# CT.net
KiCad netlist of a schematic drawn in EasyEDA
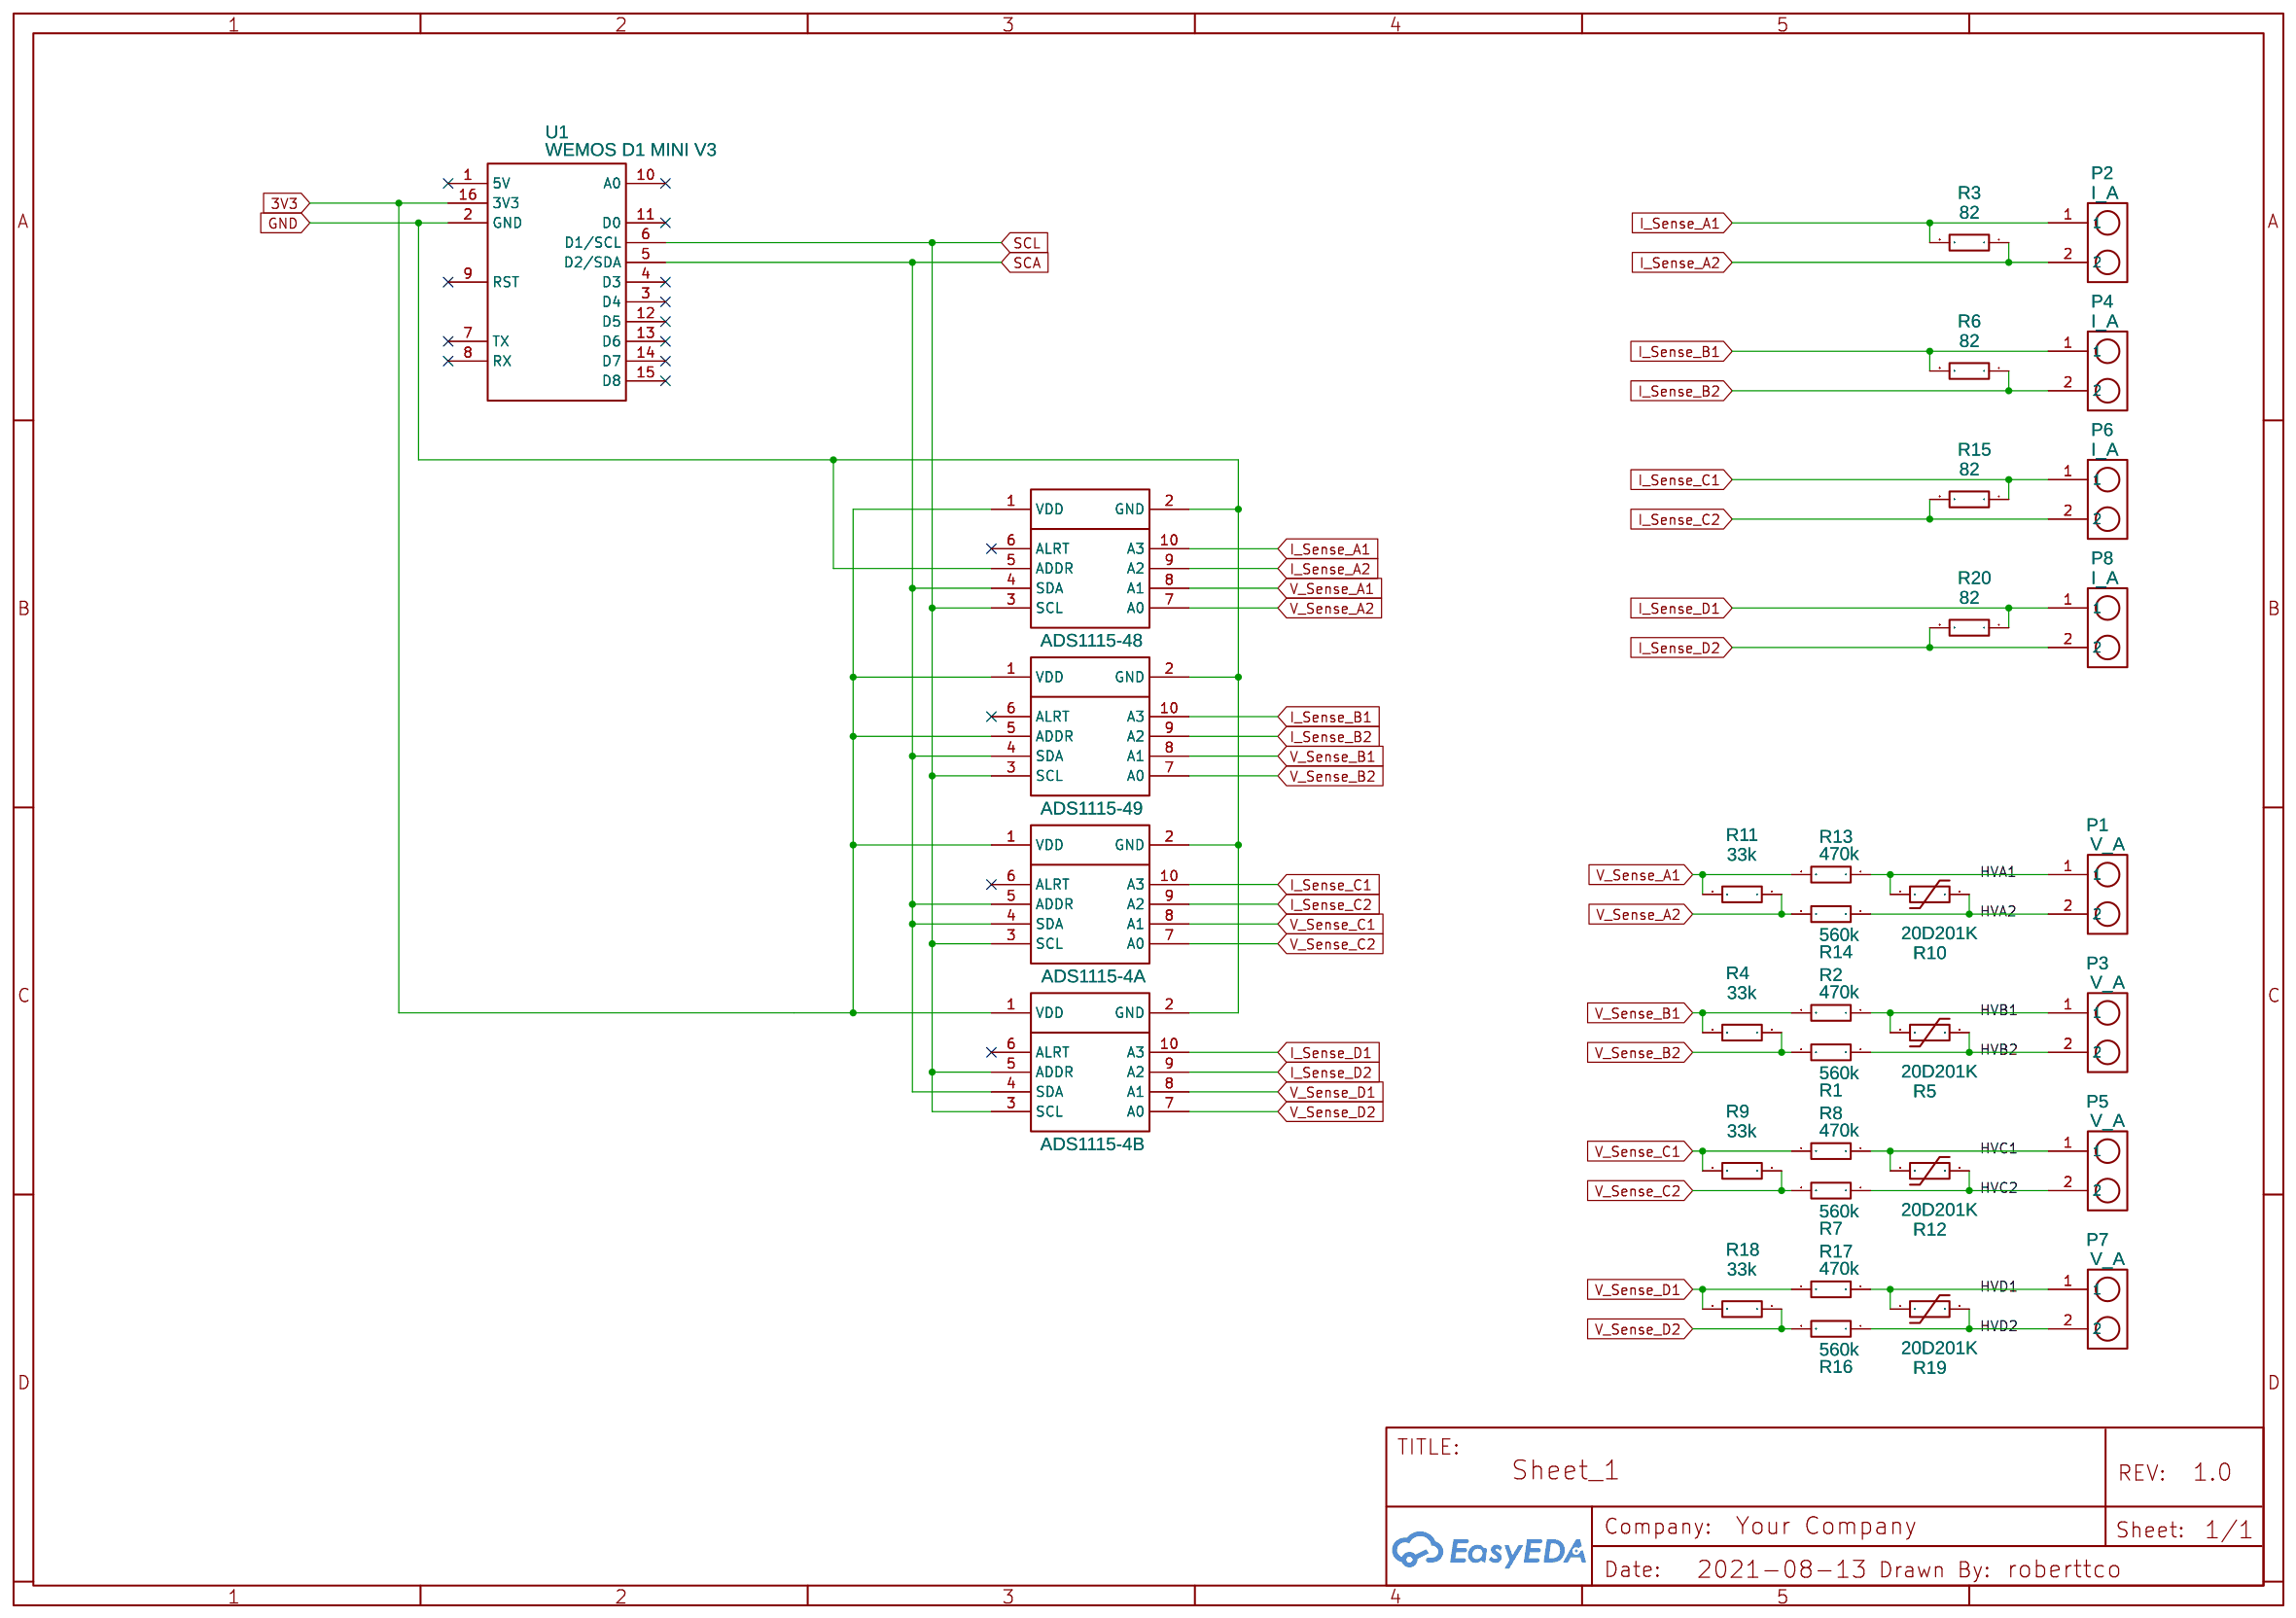
[diagram p0: schematic sheet]

(export (version "E")
  (design (tool "Eeschema 10.0.6"))
  (components
    (comp (ref "A1") (value "ADS1115-49") (libsource (lib "") (part "ADS1115")))
    (comp (ref "A2") (value "ADS1115-4A") (libsource (lib "") (part "ADS1115")))
    (comp (ref "A3") (value "ADS1115-4B") (libsource (lib "") (part "ADS1115")))
    (comp (ref "A4") (value "ADS1115-48") (libsource (lib "") (part "ADS1115")))
    (comp (ref "P1")
      (value "V_A")
      (fields (field (name "BOM_Manufacturer Part") "DW"))
      (libsource (lib "") (part "Screw Connector x2"))
    )
    (comp (ref "P2")
      (value "I_A")
      (fields (field (name "BOM_Manufacturer Part") "DW"))
      (libsource (lib "") (part "Screw Connector x2"))
    )
    (comp (ref "P3")
      (value "V_A")
      (fields (field (name "BOM_Manufacturer Part") "DW"))
      (libsource (lib "") (part "Screw Connector x2"))
    )
    (comp (ref "P4")
      (value "I_A")
      (fields (field (name "BOM_Manufacturer Part") "DW"))
      (libsource (lib "") (part "Screw Connector x2"))
    )
    (comp (ref "P5")
      (value "V_A")
      (fields (field (name "BOM_Manufacturer Part") "DW"))
      (libsource (lib "") (part "Screw Connector x2"))
    )
    (comp (ref "P6")
      (value "I_A")
      (fields (field (name "BOM_Manufacturer Part") "DW"))
      (libsource (lib "") (part "Screw Connector x2"))
    )
    (comp (ref "P7")
      (value "V_A")
      (fields (field (name "BOM_Manufacturer Part") "DW"))
      (libsource (lib "") (part "Screw Connector x2"))
    )
    (comp (ref "P8")
      (value "I_A")
      (fields (field (name "BOM_Manufacturer Part") "DW"))
      (libsource (lib "") (part "Screw Connector x2"))
    )
    (comp (ref "R1")
      (value "560k")
      (fields (field (name "BOM_Supplier Part") "C119347"))
      (libsource (lib "") (part "RESISTOR"))
    )
    (comp (ref "R2")
      (value "470k")
      (fields (field (name "BOM_Supplier Part") "C119347"))
      (libsource (lib "") (part "RESISTOR"))
    )
    (comp (ref "R3")
      (value "82")
      (fields (field (name "BOM_Supplier Part") "C119347"))
      (libsource (lib "") (part "RESISTOR"))
    )
    (comp (ref "R4")
      (value "33k")
      (fields (field (name "BOM_Supplier Part") "C119347"))
      (libsource (lib "") (part "RESISTOR"))
    )
    (comp (ref "R5")
      (value "20D201K")
      (fields (field (name "BOM_Supplier Part") "C317857"))
      (libsource (lib "") (part "20D201K"))
    )
    (comp (ref "R6")
      (value "82")
      (fields (field (name "BOM_Supplier Part") "C119347"))
      (libsource (lib "") (part "RESISTOR"))
    )
    (comp (ref "R7")
      (value "560k")
      (fields (field (name "BOM_Supplier Part") "C119347"))
      (libsource (lib "") (part "RESISTOR"))
    )
    (comp (ref "R8")
      (value "470k")
      (fields (field (name "BOM_Supplier Part") "C119347"))
      (libsource (lib "") (part "RESISTOR"))
    )
    (comp (ref "R9")
      (value "33k")
      (fields (field (name "BOM_Supplier Part") "C119347"))
      (libsource (lib "") (part "RESISTOR"))
    )
    (comp (ref "R10")
      (value "20D201K")
      (fields (field (name "BOM_Supplier Part") "C317857"))
      (libsource (lib "") (part "20D201K"))
    )
    (comp (ref "R11")
      (value "33k")
      (fields (field (name "BOM_Supplier Part") "C119347"))
      (libsource (lib "") (part "RESISTOR"))
    )
    (comp (ref "R12")
      (value "20D201K")
      (fields (field (name "BOM_Supplier Part") "C317857"))
      (libsource (lib "") (part "20D201K"))
    )
    (comp (ref "R13")
      (value "470k")
      (fields (field (name "BOM_Supplier Part") "C119347"))
      (libsource (lib "") (part "RESISTOR"))
    )
    (comp (ref "R14")
      (value "560k")
      (fields (field (name "BOM_Supplier Part") "C119347"))
      (libsource (lib "") (part "RESISTOR"))
    )
    (comp (ref "R15")
      (value "82")
      (fields (field (name "BOM_Supplier Part") "C119347"))
      (libsource (lib "") (part "RESISTOR"))
    )
    (comp (ref "R16")
      (value "560k")
      (fields (field (name "BOM_Supplier Part") "C119347"))
      (libsource (lib "") (part "RESISTOR"))
    )
    (comp (ref "R17")
      (value "470k")
      (fields (field (name "BOM_Supplier Part") "C119347"))
      (libsource (lib "") (part "RESISTOR"))
    )
    (comp (ref "R18")
      (value "33k")
      (fields (field (name "BOM_Supplier Part") "C119347"))
      (libsource (lib "") (part "RESISTOR"))
    )
    (comp (ref "R19")
      (value "20D201K")
      (fields (field (name "BOM_Supplier Part") "C317857"))
      (libsource (lib "") (part "20D201K"))
    )
    (comp (ref "R20")
      (value "82")
      (fields (field (name "BOM_Supplier Part") "C119347"))
      (libsource (lib "") (part "RESISTOR"))
    )
    (comp (ref "U1")
      (value "WEMOS D1 MINI V3")
      (fields (field (name "BOM_Manufacturer Part") "Wemos D1 mini"))
      (libsource (lib "") (part "WEMOS D1 MINI V3"))
    )
  )
  (nets
    (net (code "1") (name "/HVA1") (class "Default")
      (node (ref "P1") (pin "1") (pinfunction "1_1") (pintype "unspecified"))
      (node (ref "R10") (pin "1") (pinfunction "1_1") (pintype "unspecified"))
      (node (ref "R13") (pin "1") (pinfunction "1_1") (pintype "unspecified"))
    )
    (net (code "2") (name "/HVA2") (class "Default")
      (node (ref "P1") (pin "2") (pinfunction "2_2") (pintype "unspecified"))
      (node (ref "R10") (pin "2") (pinfunction "2_2") (pintype "unspecified"))
      (node (ref "R14") (pin "1") (pinfunction "1_1") (pintype "unspecified"))
    )
    (net (code "3") (name "/HVB1") (class "Default")
      (node (ref "P3") (pin "1") (pinfunction "1_1") (pintype "unspecified"))
      (node (ref "R2") (pin "1") (pinfunction "1_1") (pintype "unspecified"))
      (node (ref "R5") (pin "1") (pinfunction "1_1") (pintype "unspecified"))
    )
    (net (code "4") (name "/HVB2") (class "Default")
      (node (ref "P3") (pin "2") (pinfunction "2_2") (pintype "unspecified"))
      (node (ref "R1") (pin "1") (pinfunction "1_1") (pintype "unspecified"))
      (node (ref "R5") (pin "2") (pinfunction "2_2") (pintype "unspecified"))
    )
    (net (code "5") (name "/HVC1") (class "Default")
      (node (ref "P5") (pin "1") (pinfunction "1_1") (pintype "unspecified"))
      (node (ref "R12") (pin "1") (pinfunction "1_1") (pintype "unspecified"))
      (node (ref "R8") (pin "1") (pinfunction "1_1") (pintype "unspecified"))
    )
    (net (code "6") (name "/HVC2") (class "Default")
      (node (ref "P5") (pin "2") (pinfunction "2_2") (pintype "unspecified"))
      (node (ref "R12") (pin "2") (pinfunction "2_2") (pintype "unspecified"))
      (node (ref "R7") (pin "1") (pinfunction "1_1") (pintype "unspecified"))
    )
    (net (code "7") (name "/HVD1") (class "Default")
      (node (ref "P7") (pin "1") (pinfunction "1_1") (pintype "unspecified"))
      (node (ref "R17") (pin "1") (pinfunction "1_1") (pintype "unspecified"))
      (node (ref "R19") (pin "1") (pinfunction "1_1") (pintype "unspecified"))
    )
    (net (code "8") (name "/HVD2") (class "Default")
      (node (ref "P7") (pin "2") (pinfunction "2_2") (pintype "unspecified"))
      (node (ref "R16") (pin "1") (pinfunction "1_1") (pintype "unspecified"))
      (node (ref "R19") (pin "2") (pinfunction "2_2") (pintype "unspecified"))
    )
    (net (code "9") (name "3V3") (class "Default")
      (node (ref "A1") (pin "1") (pinfunction "VDD_1") (pintype "passive"))
      (node (ref "A1") (pin "5") (pinfunction "ADDR_5") (pintype "output"))
      (node (ref "A2") (pin "1") (pinfunction "VDD_1") (pintype "passive"))
      (node (ref "A3") (pin "1") (pinfunction "VDD_1") (pintype "passive"))
      (node (ref "A4") (pin "1") (pinfunction "VDD_1") (pintype "passive"))
      (node (ref "U1") (pin "16") (pinfunction "3V3_16") (pintype "unspecified"))
    )
    (net (code "10") (name "GND") (class "Default")
      (node (ref "A1") (pin "2") (pinfunction "GND_2") (pintype "passive"))
      (node (ref "A2") (pin "2") (pinfunction "GND_2") (pintype "passive"))
      (node (ref "A3") (pin "2") (pinfunction "GND_2") (pintype "passive"))
      (node (ref "A4") (pin "2") (pinfunction "GND_2") (pintype "passive"))
      (node (ref "A4") (pin "5") (pinfunction "ADDR_5") (pintype "output"))
      (node (ref "U1") (pin "2") (pinfunction "GND_2") (pintype "unspecified"))
    )
    (net (code "11") (name "I_Sense_A1") (class "Default")
      (node (ref "A4") (pin "10") (pinfunction "A3_10") (pintype "input"))
      (node (ref "P2") (pin "1") (pinfunction "1_1") (pintype "unspecified"))
      (node (ref "R3") (pin "2") (pinfunction "2_2") (pintype "unspecified"))
    )
    (net (code "12") (name "I_Sense_A2") (class "Default")
      (node (ref "A4") (pin "9") (pinfunction "A2_9") (pintype "input"))
      (node (ref "P2") (pin "2") (pinfunction "2_2") (pintype "unspecified"))
      (node (ref "R3") (pin "1") (pinfunction "1_1") (pintype "unspecified"))
    )
    (net (code "13") (name "I_Sense_B1") (class "Default")
      (node (ref "A1") (pin "10") (pinfunction "A3_10") (pintype "input"))
      (node (ref "P4") (pin "1") (pinfunction "1_1") (pintype "unspecified"))
      (node (ref "R6") (pin "2") (pinfunction "2_2") (pintype "unspecified"))
    )
    (net (code "14") (name "I_Sense_B2") (class "Default")
      (node (ref "A1") (pin "9") (pinfunction "A2_9") (pintype "input"))
      (node (ref "P4") (pin "2") (pinfunction "2_2") (pintype "unspecified"))
      (node (ref "R6") (pin "1") (pinfunction "1_1") (pintype "unspecified"))
    )
    (net (code "15") (name "I_Sense_C1") (class "Default")
      (node (ref "A2") (pin "10") (pinfunction "A3_10") (pintype "input"))
      (node (ref "P6") (pin "1") (pinfunction "1_1") (pintype "unspecified"))
      (node (ref "R15") (pin "1") (pinfunction "1_1") (pintype "unspecified"))
    )
    (net (code "16") (name "I_Sense_C2") (class "Default")
      (node (ref "A2") (pin "9") (pinfunction "A2_9") (pintype "input"))
      (node (ref "P6") (pin "2") (pinfunction "2_2") (pintype "unspecified"))
      (node (ref "R15") (pin "2") (pinfunction "2_2") (pintype "unspecified"))
    )
    (net (code "17") (name "I_Sense_D1") (class "Default")
      (node (ref "A3") (pin "10") (pinfunction "A3_10") (pintype "input"))
      (node (ref "P8") (pin "1") (pinfunction "1_1") (pintype "unspecified"))
      (node (ref "R20") (pin "1") (pinfunction "1_1") (pintype "unspecified"))
    )
    (net (code "18") (name "I_Sense_D2") (class "Default")
      (node (ref "A3") (pin "9") (pinfunction "A2_9") (pintype "input"))
      (node (ref "P8") (pin "2") (pinfunction "2_2") (pintype "unspecified"))
      (node (ref "R20") (pin "2") (pinfunction "2_2") (pintype "unspecified"))
    )
    (net (code "19") (name "SCA") (class "Default")
      (node (ref "A1") (pin "4") (pinfunction "SDA_4") (pintype "bidirectional"))
      (node (ref "A2") (pin "4") (pinfunction "SDA_4") (pintype "bidirectional"))
      (node (ref "A2") (pin "5") (pinfunction "ADDR_5") (pintype "output"))
      (node (ref "A3") (pin "4") (pinfunction "SDA_4") (pintype "bidirectional"))
      (node (ref "A4") (pin "4") (pinfunction "SDA_4") (pintype "bidirectional"))
      (node (ref "U1") (pin "5") (pinfunction "D2/SDA_5") (pintype "unspecified"))
    )
    (net (code "20") (name "SCL") (class "Default")
      (node (ref "A1") (pin "3") (pinfunction "SCL_3") (pintype "bidirectional"))
      (node (ref "A2") (pin "3") (pinfunction "SCL_3") (pintype "bidirectional"))
      (node (ref "A3") (pin "3") (pinfunction "SCL_3") (pintype "bidirectional"))
      (node (ref "A3") (pin "5") (pinfunction "ADDR_5") (pintype "output"))
      (node (ref "A4") (pin "3") (pinfunction "SCL_3") (pintype "bidirectional"))
      (node (ref "U1") (pin "6") (pinfunction "D1/SCL_6") (pintype "unspecified"))
    )
    (net (code "21") (name "V_Sense_A1") (class "Default")
      (node (ref "A4") (pin "8") (pinfunction "A1_8") (pintype "input"))
      (node (ref "R11") (pin "2") (pinfunction "2_2") (pintype "unspecified"))
      (node (ref "R13") (pin "2") (pinfunction "2_2") (pintype "unspecified"))
    )
    (net (code "22") (name "V_Sense_A2") (class "Default")
      (node (ref "A4") (pin "7") (pinfunction "A0_7") (pintype "input"))
      (node (ref "R11") (pin "1") (pinfunction "1_1") (pintype "unspecified"))
      (node (ref "R14") (pin "2") (pinfunction "2_2") (pintype "unspecified"))
    )
    (net (code "23") (name "V_Sense_B1") (class "Default")
      (node (ref "A1") (pin "8") (pinfunction "A1_8") (pintype "input"))
      (node (ref "R2") (pin "2") (pinfunction "2_2") (pintype "unspecified"))
      (node (ref "R4") (pin "2") (pinfunction "2_2") (pintype "unspecified"))
    )
    (net (code "24") (name "V_Sense_B2") (class "Default")
      (node (ref "A1") (pin "7") (pinfunction "A0_7") (pintype "input"))
      (node (ref "R1") (pin "2") (pinfunction "2_2") (pintype "unspecified"))
      (node (ref "R4") (pin "1") (pinfunction "1_1") (pintype "unspecified"))
    )
    (net (code "25") (name "V_Sense_C1") (class "Default")
      (node (ref "A2") (pin "8") (pinfunction "A1_8") (pintype "input"))
      (node (ref "R8") (pin "2") (pinfunction "2_2") (pintype "unspecified"))
      (node (ref "R9") (pin "2") (pinfunction "2_2") (pintype "unspecified"))
    )
    (net (code "26") (name "V_Sense_C2") (class "Default")
      (node (ref "A2") (pin "7") (pinfunction "A0_7") (pintype "input"))
      (node (ref "R7") (pin "2") (pinfunction "2_2") (pintype "unspecified"))
      (node (ref "R9") (pin "1") (pinfunction "1_1") (pintype "unspecified"))
    )
    (net (code "27") (name "V_Sense_D1") (class "Default")
      (node (ref "A3") (pin "8") (pinfunction "A1_8") (pintype "input"))
      (node (ref "R17") (pin "2") (pinfunction "2_2") (pintype "unspecified"))
      (node (ref "R18") (pin "2") (pinfunction "2_2") (pintype "unspecified"))
    )
    (net (code "28") (name "V_Sense_D2") (class "Default")
      (node (ref "A3") (pin "7") (pinfunction "A0_7") (pintype "input"))
      (node (ref "R16") (pin "2") (pinfunction "2_2") (pintype "unspecified"))
      (node (ref "R18") (pin "1") (pinfunction "1_1") (pintype "unspecified"))
    )
    (net (code "29") (name "unconnected-(A1-ALRT-Pad6)") (class "Default")
      (node (ref "A1") (pin "6") (pinfunction "ALRT_6") (pintype "output+no_connect"))
    )
    (net (code "30") (name "unconnected-(A2-ALRT-Pad6)") (class "Default")
      (node (ref "A2") (pin "6") (pinfunction "ALRT_6") (pintype "output+no_connect"))
    )
    (net (code "31") (name "unconnected-(A3-ALRT-Pad6)") (class "Default")
      (node (ref "A3") (pin "6") (pinfunction "ALRT_6") (pintype "output+no_connect"))
    )
    (net (code "32") (name "unconnected-(A4-ALRT-Pad6)") (class "Default")
      (node (ref "A4") (pin "6") (pinfunction "ALRT_6") (pintype "output+no_connect"))
    )
    (net (code "33") (name "unconnected-(U1-5V-Pad1)") (class "Default")
      (node (ref "U1") (pin "1") (pinfunction "5V_1") (pintype "unspecified+no_connect"))
    )
    (net (code "34") (name "unconnected-(U1-A0-Pad10)") (class "Default")
      (node (ref "U1") (pin "10") (pinfunction "A0_10") (pintype "unspecified+no_connect"))
    )
    (net (code "35") (name "unconnected-(U1-D0-Pad11)") (class "Default")
      (node (ref "U1") (pin "11") (pinfunction "D0_11") (pintype "unspecified+no_connect"))
    )
    (net (code "36") (name "unconnected-(U1-D3-Pad4)") (class "Default")
      (node (ref "U1") (pin "4") (pinfunction "D3_4") (pintype "unspecified+no_connect"))
    )
    (net (code "37") (name "unconnected-(U1-D4-Pad3)") (class "Default")
      (node (ref "U1") (pin "3") (pinfunction "D4_3") (pintype "unspecified+no_connect"))
    )
    (net (code "38") (name "unconnected-(U1-D5-Pad12)") (class "Default")
      (node (ref "U1") (pin "12") (pinfunction "D5_12") (pintype "unspecified+no_connect"))
    )
    (net (code "39") (name "unconnected-(U1-D6-Pad13)") (class "Default")
      (node (ref "U1") (pin "13") (pinfunction "D6_13") (pintype "unspecified+no_connect"))
    )
    (net (code "40") (name "unconnected-(U1-D7-Pad14)") (class "Default")
      (node (ref "U1") (pin "14") (pinfunction "D7_14") (pintype "unspecified+no_connect"))
    )
    (net (code "41") (name "unconnected-(U1-D8-Pad15)") (class "Default")
      (node (ref "U1") (pin "15") (pinfunction "D8_15") (pintype "unspecified+no_connect"))
    )
    (net (code "42") (name "unconnected-(U1-RST-Pad9)") (class "Default")
      (node (ref "U1") (pin "9") (pinfunction "RST_9") (pintype "unspecified+no_connect"))
    )
    (net (code "43") (name "unconnected-(U1-RX-Pad8)") (class "Default")
      (node (ref "U1") (pin "8") (pinfunction "RX_8") (pintype "unspecified+no_connect"))
    )
    (net (code "44") (name "unconnected-(U1-TX-Pad7)") (class "Default")
      (node (ref "U1") (pin "7") (pinfunction "TX_7") (pintype "unspecified+no_connect"))
    )
  )
)
